# mainBoard.net
KiCad netlist of a schematic drawn in EAGLE
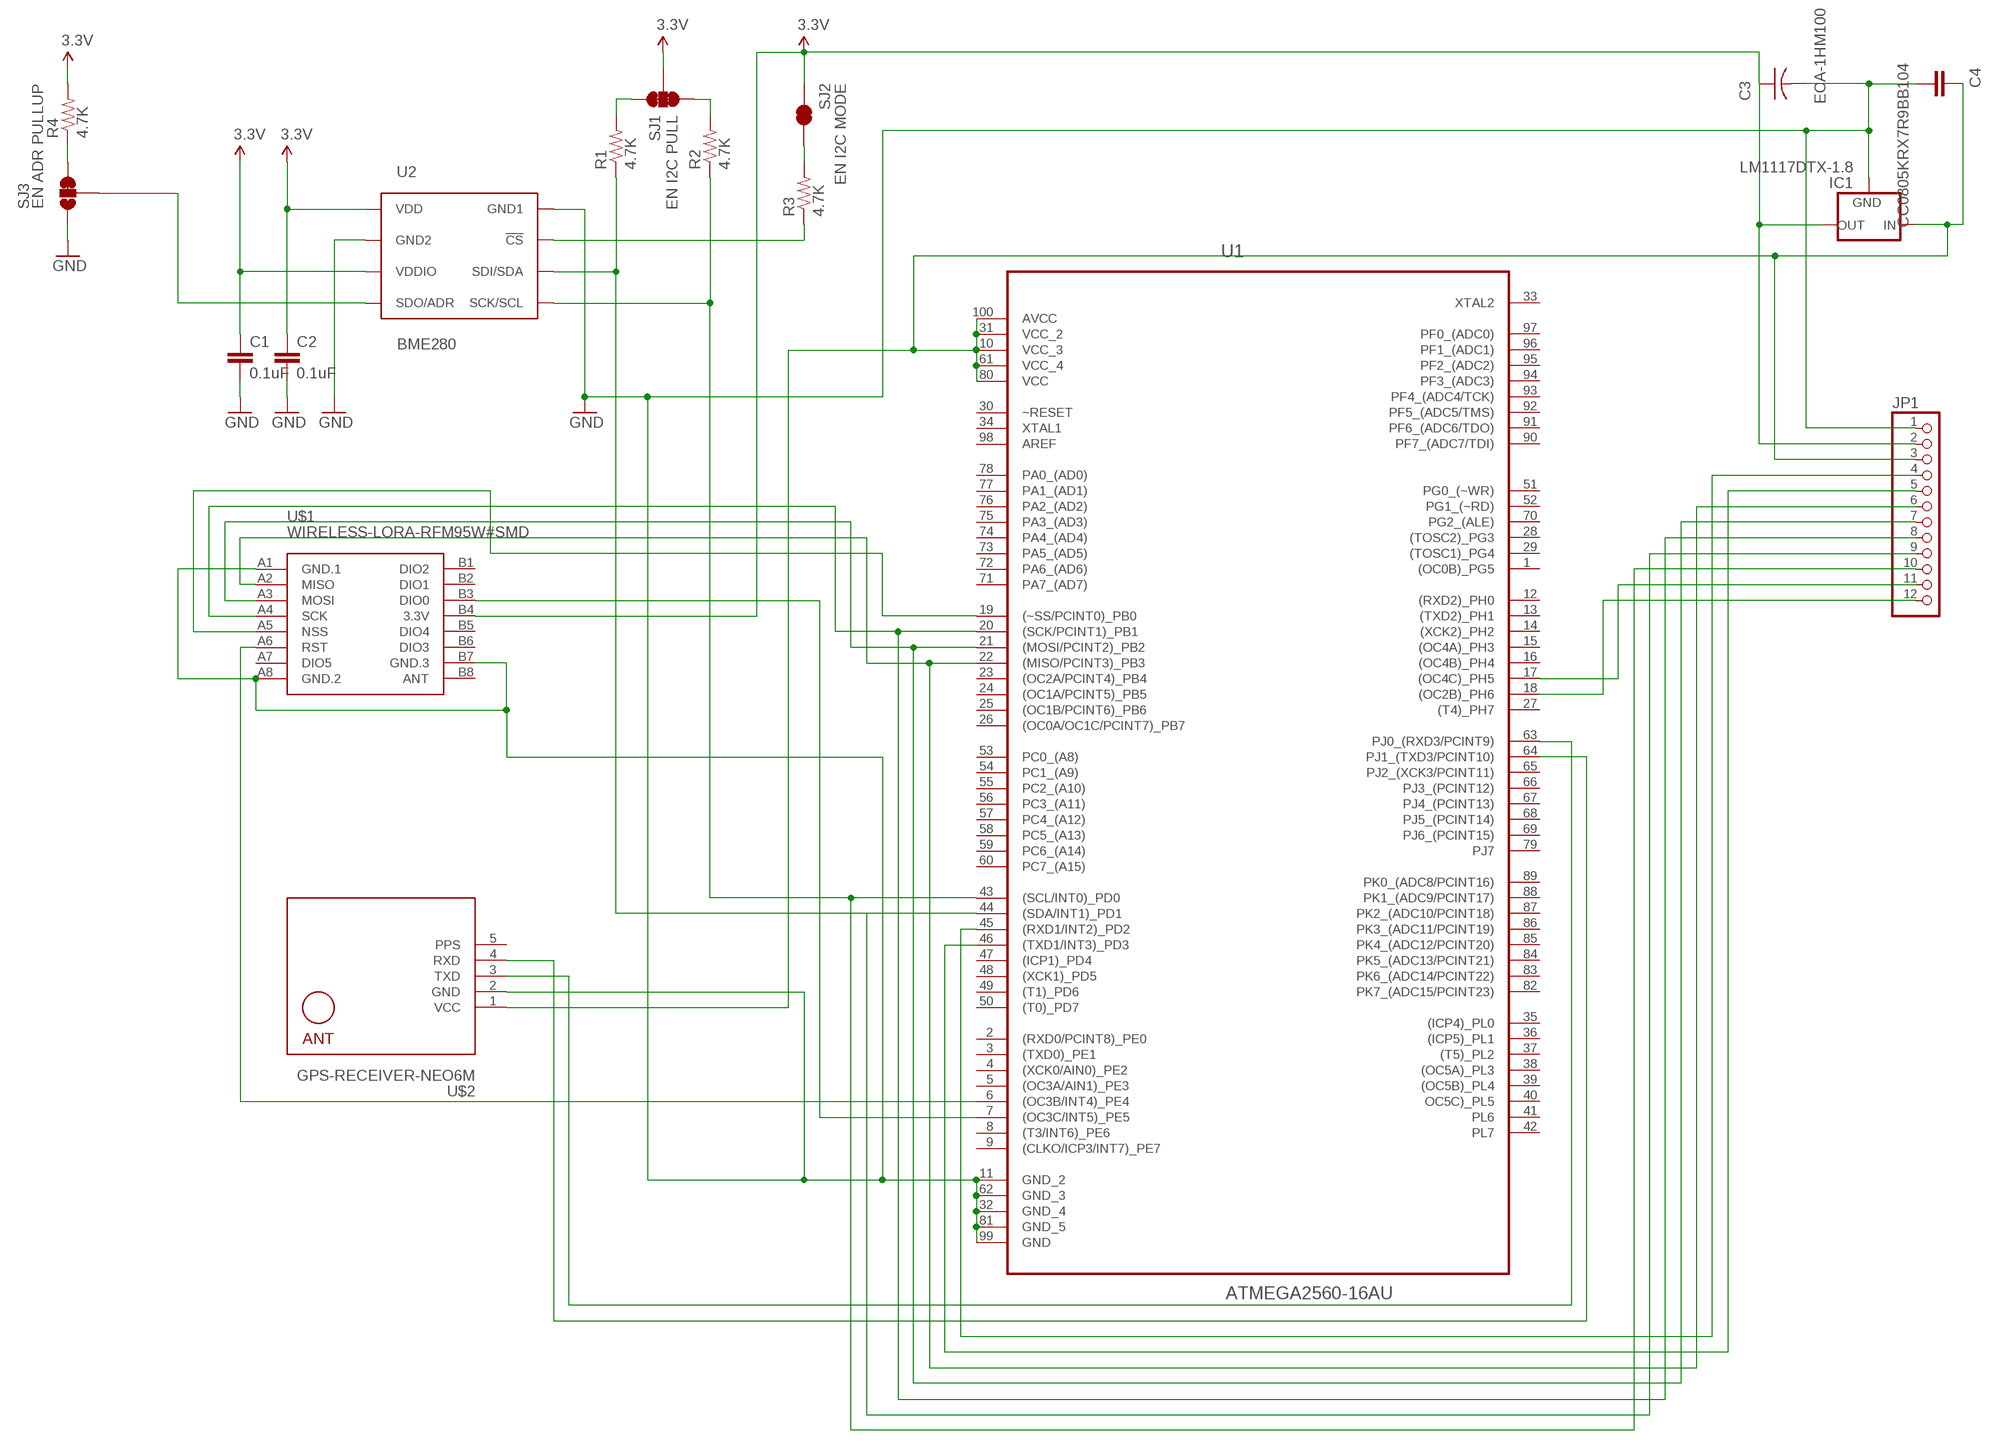
[diagram p0: schematic, sheet 1]

(export (version "E")
  (design (tool "Eeschema 10.0.6"))
  (components
    (comp (ref "C1")
      (value "0.1uF")
      (footprint "eagle-import:0603-CAP")
      (libsource (lib "eagle-import") (part "0.1UF-25V-5%(0603)"))
    )
    (comp (ref "C2")
      (value "0.1uF")
      (footprint "eagle-import:0603-CAP")
      (libsource (lib "eagle-import") (part "0.1UF-25V-5%(0603)"))
    )
    (comp (ref "C3")
      (value "ECA-1HM100")
      (footprint "eagle-import:CAP_RADIAL_2MM")
      (fields
        (field (name "DIGIKEY_PART_NUMBER") "P5178-ND")
        (field (name "MANUFACTURER") "Panasonic Electronic Components")
        (field (name "CREATED_BY") "PCBLayout.com")
      )
      (libsource (lib "eagle-import") (part "ECA-1HM100"))
    )
    (comp (ref "C4")
      (value "CC0805KRX7R9BB104")
      (footprint "eagle-import:CAP_0805")
      (fields
        (field (name "DIGIKEY_PART_NUMBER") "311-1140-2-ND")
        (field (name "MANUFACTURER") "Yageo")
        (field (name "CREATED_BY") "PCBLayout.com")
      )
      (libsource (lib "eagle-import") (part "CC0805KRX7R9BB104"))
    )
    (comp (ref "IC1")
      (value "LM1117DTX-1.8")
      (footprint "eagle-import:TO252")
      (libsource (lib "eagle-import") (part "LM1117DTX-1.8"))
    )
    (comp (ref "JP1")
      (value "PINHD-1X12")
      (footprint "eagle-import:1X12")
      (libsource (lib "eagle-import") (part "PINHD-1X12"))
    )
    (comp (ref "R1")
      (value "4.7K")
      (footprint "eagle-import:0603-RES")
      (libsource (lib "eagle-import") (part "4.7KOHM-1/10W-1%(0603)"))
    )
    (comp (ref "R2")
      (value "4.7K")
      (footprint "eagle-import:0603-RES")
      (libsource (lib "eagle-import") (part "4.7KOHM-1/10W-1%(0603)"))
    )
    (comp (ref "R3")
      (value "4.7K")
      (footprint "eagle-import:0603-RES")
      (libsource (lib "eagle-import") (part "4.7KOHM-1/10W-1%(0603)"))
    )
    (comp (ref "R4")
      (value "4.7K")
      (footprint "eagle-import:0603-RES")
      (libsource (lib "eagle-import") (part "4.7KOHM-1/10W-1%(0603)"))
    )
    (comp (ref "SJ1")
      (value "EN I2C PULL")
      (footprint "eagle-import:PAD-JUMPER-3-3OF3_NC_BY_TRACE_YES_SILK_FULL_BOX")
      (libsource (lib "eagle-import") (part "JUMPER-PAD-3-NC_BY_TRACE"))
    )
    (comp (ref "SJ2")
      (value "EN I2C MODE")
      (footprint "eagle-import:PAD-JUMPER-2-NC_BY_TRACE_YES_SILK")
      (libsource (lib "eagle-import") (part "JUMPER-PAD-2-NC_BY_TRACE"))
    )
    (comp (ref "SJ3")
      (value "EN ADR PULLUP")
      (footprint "eagle-import:PAD-JUMPER-3-2OF3_NC_BY_TRACE_YES_SILK_FULL_BOX")
      (libsource (lib "eagle-import") (part "JUMPER-PAD-3-2OF3_NC_BY_TRACE_SMALL"))
    )
    (comp (ref "U$1")
      (value "WIRELESS-LORA-RFM95W#SMD")
      (footprint "eagle-import:WIRELESS-LORA-RFM95W#SMD")
      (libsource (lib "eagle-import") (part "WIRELESS-LORA-RFM95W#SMD"))
    )
    (comp (ref "U$2")
      (value "GPS-RECEIVER-NEO6M")
      (footprint "eagle-import:GPS-RECEIVER-NEO6M")
      (libsource (lib "eagle-import") (part "GPS-RECEIVER-NEO6M"))
    )
    (comp (ref "U1")
      (value "ATMEGA2560-16AU")
      (footprint "eagle-import:QFP50P1600X1600X120-100N")
      (fields (field (name "MF") "Microchip"))
      (libsource (lib "eagle-import") (part "ATMEGA2560-16AU"))
    )
    (comp (ref "U2")
      (value "BME280")
      (footprint "eagle-import:BME280_LGA")
      (libsource (lib "eagle-import") (part "BME280"))
    )
  )
  (nets
    (net (code "1") (name "/PPS") (class "Default")
      (node (ref "U$2") (pin "5") (pinfunction "PPS_5") (pintype "power_in"))
    )
    (net (code "2") (name "3.3V") (class "Default")
      (node (ref "C1") (pin "1") (pinfunction "1_1") (pintype "passive"))
      (node (ref "C2") (pin "1") (pinfunction "1_1") (pintype "passive"))
      (node (ref "C3") (pin "1") (pinfunction "1_1") (pintype "passive"))
      (node (ref "IC1") (pin "TAB") (pinfunction "OUT_TAB") (pintype "passive"))
      (node (ref "JP1") (pin "2") (pinfunction "2_2") (pintype "passive"))
      (node (ref "R4") (pin "2") (pinfunction "2_2") (pintype "passive"))
      (node (ref "SJ1") (pin "2") (pinfunction "2_2") (pintype "passive"))
      (node (ref "SJ2") (pin "2") (pinfunction "2_2") (pintype "passive"))
      (node (ref "U$1") (pin "B4") (pinfunction "3.3V_B4") (pintype "power_in"))
      (node (ref "U2") (pin "P$6") (pinfunction "VDDIO_P$6") (pintype "bidirectional"))
      (node (ref "U2") (pin "P$8") (pinfunction "VDD_P$8") (pintype "bidirectional"))
    )
    (net (code "3") (name "GND") (class "Default")
      (node (ref "C1") (pin "2") (pinfunction "2_2") (pintype "passive"))
      (node (ref "C2") (pin "2") (pinfunction "2_2") (pintype "passive"))
      (node (ref "C3") (pin "2") (pinfunction "2_2") (pintype "passive"))
      (node (ref "C4") (pin "2") (pinfunction "2_2") (pintype "passive"))
      (node (ref "IC1") (pin "1") (pinfunction "GND_1") (pintype "input"))
      (node (ref "JP1") (pin "1") (pinfunction "1_1") (pintype "passive"))
      (node (ref "SJ3") (pin "1") (pinfunction "1_1") (pintype "passive"))
      (node (ref "U$1") (pin "A1") (pinfunction "GND.1_A1") (pintype "power_in"))
      (node (ref "U$1") (pin "A8") (pinfunction "GND.2_A8") (pintype "power_in"))
      (node (ref "U$1") (pin "B7") (pinfunction "GND.3_B7") (pintype "power_in"))
      (node (ref "U$2") (pin "2") (pinfunction "GND_2") (pintype "bidirectional"))
      (node (ref "U1") (pin "11") (pinfunction "GND_2_11") (pintype "passive"))
      (node (ref "U1") (pin "32") (pinfunction "GND_4_32") (pintype "passive"))
      (node (ref "U1") (pin "62") (pinfunction "GND_3_62") (pintype "passive"))
      (node (ref "U1") (pin "81") (pinfunction "GND_5_81") (pintype "passive"))
      (node (ref "U1") (pin "99") (pinfunction "GND_99") (pintype "passive"))
      (node (ref "U2") (pin "P$1") (pinfunction "GND1_P$1") (pintype "bidirectional"))
      (node (ref "U2") (pin "P$7") (pinfunction "GND2_P$7") (pintype "bidirectional"))
    )
    (net (code "4") (name "Net-(IC1-IN)") (class "Default")
      (node (ref "C4") (pin "1") (pinfunction "1_1") (pintype "passive"))
      (node (ref "IC1") (pin "2") (pinfunction "IN_2") (pintype "input"))
      (node (ref "JP1") (pin "3") (pinfunction "3_3") (pintype "passive"))
      (node (ref "U$2") (pin "1") (pinfunction "VCC_1") (pintype "bidirectional"))
      (node (ref "U1") (pin "10") (pinfunction "VCC_3_10") (pintype "power_in"))
      (node (ref "U1") (pin "100") (pinfunction "AVCC_100") (pintype "power_in"))
      (node (ref "U1") (pin "31") (pinfunction "VCC_2_31") (pintype "power_in"))
      (node (ref "U1") (pin "61") (pinfunction "VCC_4_61") (pintype "power_in"))
      (node (ref "U1") (pin "80") (pinfunction "VCC_80") (pintype "power_in"))
    )
    (net (code "5") (name "Net-(R1-Pad2)") (class "Default")
      (node (ref "R1") (pin "2") (pinfunction "2_2") (pintype "passive"))
      (node (ref "SJ1") (pin "3") (pinfunction "3_3") (pintype "passive"))
    )
    (net (code "6") (name "Net-(R2-Pad2)") (class "Default")
      (node (ref "R2") (pin "2") (pinfunction "2_2") (pintype "passive"))
      (node (ref "SJ1") (pin "1") (pinfunction "1_1") (pintype "passive"))
    )
    (net (code "7") (name "Net-(R3-Pad2)") (class "Default")
      (node (ref "R3") (pin "2") (pinfunction "2_2") (pintype "passive"))
      (node (ref "SJ2") (pin "1") (pinfunction "1_1") (pintype "passive"))
    )
    (net (code "8") (name "Net-(R4-Pad1)") (class "Default")
      (node (ref "R4") (pin "1") (pinfunction "1_1") (pintype "passive"))
      (node (ref "SJ3") (pin "3") (pinfunction "3_3") (pintype "passive"))
    )
    (net (code "9") (name "Net-(U$1-DIO0)") (class "Default")
      (node (ref "U$1") (pin "B3") (pinfunction "DIO0_B3") (pintype "bidirectional"))
      (node (ref "U1") (pin "7") (pinfunction "(OC3C/INT5)_PE5_7") (pintype "bidirectional"))
    )
    (net (code "10") (name "Net-(U$1-MISO)") (class "Default")
      (node (ref "JP1") (pin "6") (pinfunction "6_6") (pintype "passive"))
      (node (ref "U$1") (pin "A2") (pinfunction "MISO_A2") (pintype "bidirectional"))
      (node (ref "U1") (pin "22") (pinfunction "(MISO/PCINT3)_PB3_22") (pintype "bidirectional"))
    )
    (net (code "11") (name "Net-(U$1-MOSI)") (class "Default")
      (node (ref "JP1") (pin "7") (pinfunction "7_7") (pintype "passive"))
      (node (ref "U$1") (pin "A3") (pinfunction "MOSI_A3") (pintype "bidirectional"))
      (node (ref "U1") (pin "21") (pinfunction "(MOSI/PCINT2)_PB2_21") (pintype "bidirectional"))
    )
    (net (code "12") (name "Net-(U$1-NSS)") (class "Default")
      (node (ref "U$1") (pin "A5") (pinfunction "NSS_A5") (pintype "bidirectional"))
      (node (ref "U1") (pin "19") (pinfunction "(~{SS/PCINT0})_PB0_19") (pintype "bidirectional"))
    )
    (net (code "13") (name "Net-(U$1-RST)") (class "Default")
      (node (ref "U$1") (pin "A6") (pinfunction "RST_A6") (pintype "bidirectional"))
      (node (ref "U1") (pin "6") (pinfunction "(OC3B/INT4)_PE4_6") (pintype "bidirectional"))
    )
    (net (code "14") (name "Net-(U$1-SCK)") (class "Default")
      (node (ref "JP1") (pin "8") (pinfunction "8_8") (pintype "passive"))
      (node (ref "U$1") (pin "A4") (pinfunction "SCK_A4") (pintype "bidirectional"))
      (node (ref "U1") (pin "20") (pinfunction "(SCK/PCINT1)_PB1_20") (pintype "bidirectional"))
    )
    (net (code "15") (name "Net-(U$2-RXD)") (class "Default")
      (node (ref "U$2") (pin "4") (pinfunction "RXD_4") (pintype "power_in"))
      (node (ref "U1") (pin "64") (pinfunction "PJ1_(TXD3/PCINT10)_64") (pintype "bidirectional"))
    )
    (net (code "16") (name "Net-(U$2-TXD)") (class "Default")
      (node (ref "U$2") (pin "3") (pinfunction "TXD_3") (pintype "bidirectional"))
      (node (ref "U1") (pin "63") (pinfunction "PJ0_(RXD3/PCINT9)_63") (pintype "bidirectional"))
    )
    (net (code "17") (name "Net-(U1-(OC2B)_PH6)") (class "Default")
      (node (ref "JP1") (pin "12") (pinfunction "12_12") (pintype "passive"))
      (node (ref "U1") (pin "18") (pinfunction "(OC2B)_PH6_18") (pintype "bidirectional"))
    )
    (net (code "18") (name "Net-(U1-(OC4C)_PH5)") (class "Default")
      (node (ref "JP1") (pin "11") (pinfunction "11_11") (pintype "passive"))
      (node (ref "U1") (pin "17") (pinfunction "(OC4C)_PH5_17") (pintype "bidirectional"))
    )
    (net (code "19") (name "Net-(U1-(RXD1{slash}INT2)_PD2)") (class "Default")
      (node (ref "JP1") (pin "4") (pinfunction "4_4") (pintype "passive"))
      (node (ref "U1") (pin "45") (pinfunction "(RXD1/INT2)_PD2_45") (pintype "bidirectional"))
    )
    (net (code "20") (name "Net-(U1-(SCL{slash}INT0)_PD0)") (class "Default")
      (node (ref "JP1") (pin "10") (pinfunction "10_10") (pintype "passive"))
      (node (ref "R2") (pin "1") (pinfunction "1_1") (pintype "passive"))
      (node (ref "U1") (pin "43") (pinfunction "(SCL/INT0)_PD0_43") (pintype "bidirectional"))
      (node (ref "U2") (pin "P$4") (pinfunction "SCK/SCL_P$4") (pintype "bidirectional"))
    )
    (net (code "21") (name "Net-(U1-(SDA{slash}INT1)_PD1)") (class "Default")
      (node (ref "JP1") (pin "9") (pinfunction "9_9") (pintype "passive"))
      (node (ref "R1") (pin "1") (pinfunction "1_1") (pintype "passive"))
      (node (ref "U1") (pin "44") (pinfunction "(SDA/INT1)_PD1_44") (pintype "bidirectional"))
      (node (ref "U2") (pin "P$3") (pinfunction "SDI/SDA_P$3") (pintype "bidirectional"))
    )
    (net (code "22") (name "Net-(U1-(TXD1{slash}INT3)_PD3)") (class "Default")
      (node (ref "JP1") (pin "5") (pinfunction "5_5") (pintype "passive"))
      (node (ref "U1") (pin "46") (pinfunction "(TXD1/INT3)_PD3_46") (pintype "bidirectional"))
    )
    (net (code "23") (name "Net-(U2-SDO{slash}ADR)") (class "Default")
      (node (ref "SJ3") (pin "2") (pinfunction "2_2") (pintype "passive"))
      (node (ref "U2") (pin "P$5") (pinfunction "SDO/ADR_P$5") (pintype "bidirectional"))
    )
    (net (code "24") (name "Net-(U2-~{CS})") (class "Default")
      (node (ref "R3") (pin "1") (pinfunction "1_1") (pintype "passive"))
      (node (ref "U2") (pin "P$2") (pinfunction "~{CS}_P$2") (pintype "bidirectional"))
    )
    (net (code "25") (name "unconnected-(U$1-ANT-PadB8)") (class "Default")
      (node (ref "U$1") (pin "B8") (pinfunction "ANT_B8") (pintype "passive"))
    )
    (net (code "26") (name "unconnected-(U$1-DIO1-PadB2)") (class "Default")
      (node (ref "U$1") (pin "B2") (pinfunction "DIO1_B2") (pintype "bidirectional"))
    )
    (net (code "27") (name "unconnected-(U$1-DIO2-PadB1)") (class "Default")
      (node (ref "U$1") (pin "B1") (pinfunction "DIO2_B1") (pintype "bidirectional"))
    )
    (net (code "28") (name "unconnected-(U$1-DIO3-PadB6)") (class "Default")
      (node (ref "U$1") (pin "B6") (pinfunction "DIO3_B6") (pintype "bidirectional"))
    )
    (net (code "29") (name "unconnected-(U$1-DIO4-PadB5)") (class "Default")
      (node (ref "U$1") (pin "B5") (pinfunction "DIO4_B5") (pintype "bidirectional"))
    )
    (net (code "30") (name "unconnected-(U$1-DIO5-PadA7)") (class "Default")
      (node (ref "U$1") (pin "A7") (pinfunction "DIO5_A7") (pintype "bidirectional"))
    )
    (net (code "31") (name "unconnected-(U1-(CLKO{slash}ICP3{slash}INT7)_PE7-Pad9)") (class "Default")
      (node (ref "U1") (pin "9") (pinfunction "(CLKO/ICP3/INT7)_PE7_9") (pintype "bidirectional"))
    )
    (net (code "32") (name "unconnected-(U1-(ICP1)_PD4-Pad47)") (class "Default")
      (node (ref "U1") (pin "47") (pinfunction "(ICP1)_PD4_47") (pintype "bidirectional"))
    )
    (net (code "33") (name "unconnected-(U1-(ICP4)_PL0-Pad35)") (class "Default")
      (node (ref "U1") (pin "35") (pinfunction "(ICP4)_PL0_35") (pintype "bidirectional"))
    )
    (net (code "34") (name "unconnected-(U1-(ICP5)_PL1-Pad36)") (class "Default")
      (node (ref "U1") (pin "36") (pinfunction "(ICP5)_PL1_36") (pintype "bidirectional"))
    )
    (net (code "35") (name "unconnected-(U1-(OC0A{slash}OC1C{slash}PCINT7)_PB7-Pad26)") (class "Default")
      (node (ref "U1") (pin "26") (pinfunction "(OC0A/OC1C/PCINT7)_PB7_26") (pintype "bidirectional"))
    )
    (net (code "36") (name "unconnected-(U1-(OC0B)_PG5-Pad1)") (class "Default")
      (node (ref "U1") (pin "1") (pinfunction "(OC0B)_PG5_1") (pintype "bidirectional"))
    )
    (net (code "37") (name "unconnected-(U1-(OC1A{slash}PCINT5)_PB5-Pad24)") (class "Default")
      (node (ref "U1") (pin "24") (pinfunction "(OC1A/PCINT5)_PB5_24") (pintype "bidirectional"))
    )
    (net (code "38") (name "unconnected-(U1-(OC1B{slash}PCINT6)_PB6-Pad25)") (class "Default")
      (node (ref "U1") (pin "25") (pinfunction "(OC1B/PCINT6)_PB6_25") (pintype "bidirectional"))
    )
    (net (code "39") (name "unconnected-(U1-(OC2A{slash}PCINT4)_PB4-Pad23)") (class "Default")
      (node (ref "U1") (pin "23") (pinfunction "(OC2A/PCINT4)_PB4_23") (pintype "bidirectional"))
    )
    (net (code "40") (name "unconnected-(U1-(OC3A{slash}AIN1)_PE3-Pad5)") (class "Default")
      (node (ref "U1") (pin "5") (pinfunction "(OC3A/AIN1)_PE3_5") (pintype "bidirectional"))
    )
    (net (code "41") (name "unconnected-(U1-(OC4A)_PH3-Pad15)") (class "Default")
      (node (ref "U1") (pin "15") (pinfunction "(OC4A)_PH3_15") (pintype "bidirectional"))
    )
    (net (code "42") (name "unconnected-(U1-(OC4B)_PH4-Pad16)") (class "Default")
      (node (ref "U1") (pin "16") (pinfunction "(OC4B)_PH4_16") (pintype "bidirectional"))
    )
    (net (code "43") (name "unconnected-(U1-(OC5A)_PL3-Pad38)") (class "Default")
      (node (ref "U1") (pin "38") (pinfunction "(OC5A)_PL3_38") (pintype "bidirectional"))
    )
    (net (code "44") (name "unconnected-(U1-(OC5B)_PL4-Pad39)") (class "Default")
      (node (ref "U1") (pin "39") (pinfunction "(OC5B)_PL4_39") (pintype "bidirectional"))
    )
    (net (code "45") (name "unconnected-(U1-(RXD0{slash}PCINT8)_PE0-Pad2)") (class "Default")
      (node (ref "U1") (pin "2") (pinfunction "(RXD0/PCINT8)_PE0_2") (pintype "bidirectional"))
    )
    (net (code "46") (name "unconnected-(U1-(RXD2)_PH0-Pad12)") (class "Default")
      (node (ref "U1") (pin "12") (pinfunction "(RXD2)_PH0_12") (pintype "bidirectional"))
    )
    (net (code "47") (name "unconnected-(U1-(T0)_PD7-Pad50)") (class "Default")
      (node (ref "U1") (pin "50") (pinfunction "(T0)_PD7_50") (pintype "bidirectional"))
    )
    (net (code "48") (name "unconnected-(U1-(T1)_PD6-Pad49)") (class "Default")
      (node (ref "U1") (pin "49") (pinfunction "(T1)_PD6_49") (pintype "bidirectional"))
    )
    (net (code "49") (name "unconnected-(U1-(T3{slash}INT6)_PE6-Pad8)") (class "Default")
      (node (ref "U1") (pin "8") (pinfunction "(T3/INT6)_PE6_8") (pintype "bidirectional"))
    )
    (net (code "50") (name "unconnected-(U1-(T4)_PH7-Pad27)") (class "Default")
      (node (ref "U1") (pin "27") (pinfunction "(T4)_PH7_27") (pintype "bidirectional"))
    )
    (net (code "51") (name "unconnected-(U1-(T5)_PL2-Pad37)") (class "Default")
      (node (ref "U1") (pin "37") (pinfunction "(T5)_PL2_37") (pintype "bidirectional"))
    )
    (net (code "52") (name "unconnected-(U1-(TOSC1)_PG4-Pad29)") (class "Default")
      (node (ref "U1") (pin "29") (pinfunction "(TOSC1)_PG4_29") (pintype "bidirectional"))
    )
    (net (code "53") (name "unconnected-(U1-(TOSC2)_PG3-Pad28)") (class "Default")
      (node (ref "U1") (pin "28") (pinfunction "(TOSC2)_PG3_28") (pintype "bidirectional"))
    )
    (net (code "54") (name "unconnected-(U1-(TXD0)_PE1-Pad3)") (class "Default")
      (node (ref "U1") (pin "3") (pinfunction "(TXD0)_PE1_3") (pintype "bidirectional"))
    )
    (net (code "55") (name "unconnected-(U1-(TXD2)_PH1-Pad13)") (class "Default")
      (node (ref "U1") (pin "13") (pinfunction "(TXD2)_PH1_13") (pintype "bidirectional"))
    )
    (net (code "56") (name "unconnected-(U1-(XCK0{slash}AIN0)_PE2-Pad4)") (class "Default")
      (node (ref "U1") (pin "4") (pinfunction "(XCK0/AIN0)_PE2_4") (pintype "bidirectional"))
    )
    (net (code "57") (name "unconnected-(U1-(XCK1)_PD5-Pad48)") (class "Default")
      (node (ref "U1") (pin "48") (pinfunction "(XCK1)_PD5_48") (pintype "bidirectional"))
    )
    (net (code "58") (name "unconnected-(U1-(XCK2)_PH2-Pad14)") (class "Default")
      (node (ref "U1") (pin "14") (pinfunction "(XCK2)_PH2_14") (pintype "bidirectional"))
    )
    (net (code "59") (name "unconnected-(U1-AREF-Pad98)") (class "Default")
      (node (ref "U1") (pin "98") (pinfunction "AREF_98") (pintype "input"))
    )
    (net (code "60") (name "unconnected-(U1-OC5C)_PL5-Pad40)") (class "Default")
      (node (ref "U1") (pin "40") (pinfunction "OC5C)_PL5_40") (pintype "bidirectional"))
    )
    (net (code "61") (name "unconnected-(U1-PA0_(AD0)-Pad78)") (class "Default")
      (node (ref "U1") (pin "78") (pinfunction "PA0_(AD0)_78") (pintype "bidirectional"))
    )
    (net (code "62") (name "unconnected-(U1-PA1_(AD1)-Pad77)") (class "Default")
      (node (ref "U1") (pin "77") (pinfunction "PA1_(AD1)_77") (pintype "bidirectional"))
    )
    (net (code "63") (name "unconnected-(U1-PA2_(AD2)-Pad76)") (class "Default")
      (node (ref "U1") (pin "76") (pinfunction "PA2_(AD2)_76") (pintype "bidirectional"))
    )
    (net (code "64") (name "unconnected-(U1-PA3_(AD3)-Pad75)") (class "Default")
      (node (ref "U1") (pin "75") (pinfunction "PA3_(AD3)_75") (pintype "bidirectional"))
    )
    (net (code "65") (name "unconnected-(U1-PA4_(AD4)-Pad74)") (class "Default")
      (node (ref "U1") (pin "74") (pinfunction "PA4_(AD4)_74") (pintype "bidirectional"))
    )
    (net (code "66") (name "unconnected-(U1-PA5_(AD5)-Pad73)") (class "Default")
      (node (ref "U1") (pin "73") (pinfunction "PA5_(AD5)_73") (pintype "bidirectional"))
    )
    (net (code "67") (name "unconnected-(U1-PA6_(AD6)-Pad72)") (class "Default")
      (node (ref "U1") (pin "72") (pinfunction "PA6_(AD6)_72") (pintype "bidirectional"))
    )
    (net (code "68") (name "unconnected-(U1-PA7_(AD7)-Pad71)") (class "Default")
      (node (ref "U1") (pin "71") (pinfunction "PA7_(AD7)_71") (pintype "bidirectional"))
    )
    (net (code "69") (name "unconnected-(U1-PC0_(A8)-Pad53)") (class "Default")
      (node (ref "U1") (pin "53") (pinfunction "PC0_(A8)_53") (pintype "bidirectional"))
    )
    (net (code "70") (name "unconnected-(U1-PC1_(A9)-Pad54)") (class "Default")
      (node (ref "U1") (pin "54") (pinfunction "PC1_(A9)_54") (pintype "bidirectional"))
    )
    (net (code "71") (name "unconnected-(U1-PC2_(A10)-Pad55)") (class "Default")
      (node (ref "U1") (pin "55") (pinfunction "PC2_(A10)_55") (pintype "bidirectional"))
    )
    (net (code "72") (name "unconnected-(U1-PC3_(A11)-Pad56)") (class "Default")
      (node (ref "U1") (pin "56") (pinfunction "PC3_(A11)_56") (pintype "bidirectional"))
    )
    (net (code "73") (name "unconnected-(U1-PC4_(A12)-Pad57)") (class "Default")
      (node (ref "U1") (pin "57") (pinfunction "PC4_(A12)_57") (pintype "bidirectional"))
    )
    (net (code "74") (name "unconnected-(U1-PC5_(A13)-Pad58)") (class "Default")
      (node (ref "U1") (pin "58") (pinfunction "PC5_(A13)_58") (pintype "bidirectional"))
    )
    (net (code "75") (name "unconnected-(U1-PC6_(A14)-Pad59)") (class "Default")
      (node (ref "U1") (pin "59") (pinfunction "PC6_(A14)_59") (pintype "bidirectional"))
    )
    (net (code "76") (name "unconnected-(U1-PC7_(A15)-Pad60)") (class "Default")
      (node (ref "U1") (pin "60") (pinfunction "PC7_(A15)_60") (pintype "bidirectional"))
    )
    (net (code "77") (name "unconnected-(U1-PF0_(ADC0)-Pad97)") (class "Default")
      (node (ref "U1") (pin "97") (pinfunction "PF0_(ADC0)_97") (pintype "bidirectional"))
    )
    (net (code "78") (name "unconnected-(U1-PF1_(ADC1)-Pad96)") (class "Default")
      (node (ref "U1") (pin "96") (pinfunction "PF1_(ADC1)_96") (pintype "bidirectional"))
    )
    (net (code "79") (name "unconnected-(U1-PF2_(ADC2)-Pad95)") (class "Default")
      (node (ref "U1") (pin "95") (pinfunction "PF2_(ADC2)_95") (pintype "bidirectional"))
    )
    (net (code "80") (name "unconnected-(U1-PF3_(ADC3)-Pad94)") (class "Default")
      (node (ref "U1") (pin "94") (pinfunction "PF3_(ADC3)_94") (pintype "bidirectional"))
    )
    (net (code "81") (name "unconnected-(U1-PF4_(ADC4{slash}TCK)-Pad93)") (class "Default")
      (node (ref "U1") (pin "93") (pinfunction "PF4_(ADC4/TCK)_93") (pintype "bidirectional"))
    )
    (net (code "82") (name "unconnected-(U1-PF5_(ADC5{slash}TMS)-Pad92)") (class "Default")
      (node (ref "U1") (pin "92") (pinfunction "PF5_(ADC5/TMS)_92") (pintype "bidirectional"))
    )
    (net (code "83") (name "unconnected-(U1-PF6_(ADC6{slash}TDO)-Pad91)") (class "Default")
      (node (ref "U1") (pin "91") (pinfunction "PF6_(ADC6/TDO)_91") (pintype "bidirectional"))
    )
    (net (code "84") (name "unconnected-(U1-PF7_(ADC7{slash}TDI)-Pad90)") (class "Default")
      (node (ref "U1") (pin "90") (pinfunction "PF7_(ADC7/TDI)_90") (pintype "bidirectional"))
    )
    (net (code "85") (name "unconnected-(U1-PG0_(~{WR})-Pad51)") (class "Default")
      (node (ref "U1") (pin "51") (pinfunction "PG0_(~{WR})_51") (pintype "bidirectional"))
    )
    (net (code "86") (name "unconnected-(U1-PG1_(~{RD})-Pad52)") (class "Default")
      (node (ref "U1") (pin "52") (pinfunction "PG1_(~{RD})_52") (pintype "bidirectional"))
    )
    (net (code "87") (name "unconnected-(U1-PG2_(ALE)-Pad70)") (class "Default")
      (node (ref "U1") (pin "70") (pinfunction "PG2_(ALE)_70") (pintype "bidirectional"))
    )
    (net (code "88") (name "unconnected-(U1-PJ2_(XCK3{slash}PCINT11)-Pad65)") (class "Default")
      (node (ref "U1") (pin "65") (pinfunction "PJ2_(XCK3/PCINT11)_65") (pintype "bidirectional"))
    )
    (net (code "89") (name "unconnected-(U1-PJ3_(PCINT12)-Pad66)") (class "Default")
      (node (ref "U1") (pin "66") (pinfunction "PJ3_(PCINT12)_66") (pintype "bidirectional"))
    )
    (net (code "90") (name "unconnected-(U1-PJ4_(PCINT13)-Pad67)") (class "Default")
      (node (ref "U1") (pin "67") (pinfunction "PJ4_(PCINT13)_67") (pintype "bidirectional"))
    )
    (net (code "91") (name "unconnected-(U1-PJ5_(PCINT14)-Pad68)") (class "Default")
      (node (ref "U1") (pin "68") (pinfunction "PJ5_(PCINT14)_68") (pintype "bidirectional"))
    )
    (net (code "92") (name "unconnected-(U1-PJ6_(PCINT15)-Pad69)") (class "Default")
      (node (ref "U1") (pin "69") (pinfunction "PJ6_(PCINT15)_69") (pintype "bidirectional"))
    )
    (net (code "93") (name "unconnected-(U1-PJ7-Pad79)") (class "Default")
      (node (ref "U1") (pin "79") (pinfunction "PJ7_79") (pintype "bidirectional"))
    )
    (net (code "94") (name "unconnected-(U1-PK0_(ADC8{slash}PCINT16)-Pad89)") (class "Default")
      (node (ref "U1") (pin "89") (pinfunction "PK0_(ADC8/PCINT16)_89") (pintype "bidirectional"))
    )
    (net (code "95") (name "unconnected-(U1-PK1_(ADC9{slash}PCINT17)-Pad88)") (class "Default")
      (node (ref "U1") (pin "88") (pinfunction "PK1_(ADC9/PCINT17)_88") (pintype "bidirectional"))
    )
    (net (code "96") (name "unconnected-(U1-PK2_(ADC10{slash}PCINT18)-Pad87)") (class "Default")
      (node (ref "U1") (pin "87") (pinfunction "PK2_(ADC10/PCINT18)_87") (pintype "bidirectional"))
    )
    (net (code "97") (name "unconnected-(U1-PK3_(ADC11{slash}PCINT19)-Pad86)") (class "Default")
      (node (ref "U1") (pin "86") (pinfunction "PK3_(ADC11/PCINT19)_86") (pintype "bidirectional"))
    )
    (net (code "98") (name "unconnected-(U1-PK4_(ADC12{slash}PCINT20)-Pad85)") (class "Default")
      (node (ref "U1") (pin "85") (pinfunction "PK4_(ADC12/PCINT20)_85") (pintype "bidirectional"))
    )
    (net (code "99") (name "unconnected-(U1-PK5_(ADC13{slash}PCINT21)-Pad84)") (class "Default")
      (node (ref "U1") (pin "84") (pinfunction "PK5_(ADC13/PCINT21)_84") (pintype "bidirectional"))
    )
    (net (code "100") (name "unconnected-(U1-PK6_(ADC14{slash}PCINT22)-Pad83)") (class "Default")
      (node (ref "U1") (pin "83") (pinfunction "PK6_(ADC14/PCINT22)_83") (pintype "bidirectional"))
    )
    (net (code "101") (name "unconnected-(U1-PK7_(ADC15{slash}PCINT23)-Pad82)") (class "Default")
      (node (ref "U1") (pin "82") (pinfunction "PK7_(ADC15/PCINT23)_82") (pintype "bidirectional"))
    )
    (net (code "102") (name "unconnected-(U1-PL6-Pad41)") (class "Default")
      (node (ref "U1") (pin "41") (pinfunction "PL6_41") (pintype "bidirectional"))
    )
    (net (code "103") (name "unconnected-(U1-PL7-Pad42)") (class "Default")
      (node (ref "U1") (pin "42") (pinfunction "PL7_42") (pintype "bidirectional"))
    )
    (net (code "104") (name "unconnected-(U1-XTAL1-Pad34)") (class "Default")
      (node (ref "U1") (pin "34") (pinfunction "XTAL1_34") (pintype "input"))
    )
    (net (code "105") (name "unconnected-(U1-XTAL2-Pad33)") (class "Default")
      (node (ref "U1") (pin "33") (pinfunction "XTAL2_33") (pintype "output"))
    )
    (net (code "106") (name "unconnected-(U1-~{RESET}-Pad30)") (class "Default")
      (node (ref "U1") (pin "30") (pinfunction "~{RESET}_30") (pintype "input"))
    )
  )
)
